# Voltage_regulator.net
KiCad netlist of a schematic drawn in Altium Designer
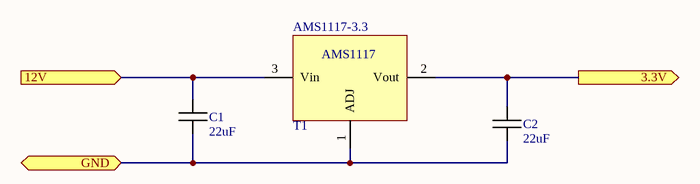
[diagram p0: Voltage regulator.SchDoc]

(export (version "E")
  (design (tool "Eeschema 10.0.6"))
  (components
    (comp (ref "AMS1117-3.3")
      (value "T1")
      (footprint "SOT-223")
      (libsource (lib "AMS1117 breakout") (part "AMS1117"))
    )
    (comp (ref "C1")
      (value "22uF")
      (footprint "0805-C")
      (libsource (lib "AMS1117 breakout") (part "Capacitor"))
    )
    (comp (ref "C2")
      (value "22uF")
      (footprint "0805-C")
      (libsource (lib "AMS1117 breakout") (part "Capacitor"))
    )
  )
  (nets
    (net (code "1") (name "/3.3V") (class "Default")
      (node (ref "AMS1117-3.3") (pin "2") (pinfunction "Vout_2") (pintype "passive"))
      (node (ref "C2") (pin "2") (pinfunction "2_2") (pintype "passive"))
    )
    (net (code "2") (name "/12V") (class "Default")
      (node (ref "AMS1117-3.3") (pin "3") (pinfunction "Vin_3") (pintype "passive"))
      (node (ref "C1") (pin "2") (pinfunction "2_2") (pintype "passive"))
    )
    (net (code "3") (name "/GND") (class "Default")
      (node (ref "AMS1117-3.3") (pin "1") (pinfunction "ADJ_1") (pintype "passive"))
      (node (ref "C1") (pin "1") (pinfunction "1_1") (pintype "passive"))
      (node (ref "C2") (pin "1") (pinfunction "1_1") (pintype "passive"))
    )
  )
)
